# BT5.net
KiCad netlist of a schematic drawn in Altium Designer
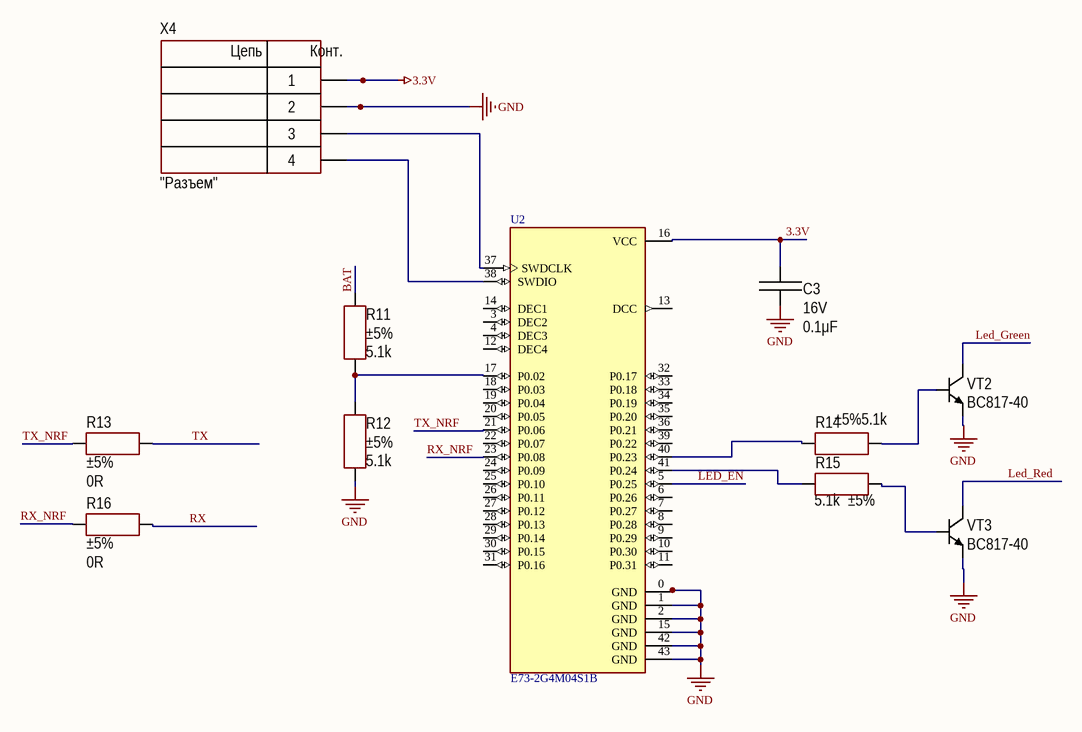
[diagram p0: BT5.SchDoc]

(export (version "E")
  (design (tool "Eeschema 10.0.6"))
  (components
    (comp (ref "C3")
      (value "0.1μF")
      (footprint "standard-case:CAP: 0805")
      (fields
        (field (name "MANUFACTURER") "Yageo")
        (field (name "PARTNUMBER") "CC0805KRX7R7BB104")
        (field (name "VALUEMANUFACTURERPARTNUMBER") "Ceramic capacitor, 0.1μF, X7R, ±10%, 16V, 0805, -55...+125°C")
        (field (name "VOLTAGE") "16V")
      )
      (libsource (lib "capacitor") (part "Ceramic_0805"))
    )
    (comp (ref "R11")
      (value "5.1k")
      (footprint "standard-case:RES: 0805")
      (fields
        (field (name "MANUFACTURER") "Yageo")
        (field (name "PARTNUMBER") "RC0805JR-075K1L")
        (field (name "VALUEMANUFACTURERPARTNUMBER") "Resistor film, 5.1k, ±5%, 0805, 0.125W, -55...+125°C")
        (field (name "TOLERANCE") "±5%")
      )
      (libsource (lib "resistor") (part "Resistor_0805"))
    )
    (comp (ref "R12")
      (value "5.1k")
      (footprint "standard-case:RES: 0805")
      (fields
        (field (name "MANUFACTURER") "Yageo")
        (field (name "PARTNUMBER") "RC0805JR-075K1L")
        (field (name "VALUEMANUFACTURERPARTNUMBER") "Resistor film, 5.1k, ±5%, 0805, 0.125W, -55...+125°C")
        (field (name "TOLERANCE") "±5%")
      )
      (libsource (lib "resistor") (part "Resistor_0805"))
    )
    (comp (ref "R13")
      (value "0R")
      (footprint "standard-case:RES: 0805")
      (fields
        (field (name "MANUFACTURER") "Yageo")
        (field (name "PARTNUMBER") "RC0805JR-070RL")
        (field (name "VALUEMANUFACTURERPARTNUMBER") "Resistor film, 0R, ±5%, 0805, 0.125W, -55...+125°C")
        (field (name "TOLERANCE") "±5%")
      )
      (libsource (lib "") (part "Resistor_0805_1"))
    )
    (comp (ref "R14")
      (value "5.1k")
      (footprint "standard-case:RES: 0805")
      (fields
        (field (name "MANUFACTURER") "Yageo")
        (field (name "PARTNUMBER") "RC0805JR-075K1L")
        (field (name "VALUEMANUFACTURERPARTNUMBER") "Resistor film, 5.1k, ±5%, 0805, 0.125W, -55...+125°C")
        (field (name "TOLERANCE") "±5%")
      )
      (libsource (lib "") (part "Resistor_0805_1"))
    )
    (comp (ref "R15")
      (value "5.1k")
      (footprint "standard-case:RES: 0805")
      (fields
        (field (name "MANUFACTURER") "Yageo")
        (field (name "PARTNUMBER") "RC0805JR-075K1L")
        (field (name "VALUEMANUFACTURERPARTNUMBER") "Resistor film, 5.1k, ±5%, 0805, 0.125W, -55...+125°C")
        (field (name "TOLERANCE") "±5%")
      )
      (libsource (lib "") (part "Resistor_0805_1"))
    )
    (comp (ref "R16")
      (value "0R")
      (footprint "standard-case:RES: 0805")
      (fields
        (field (name "MANUFACTURER") "Yageo")
        (field (name "PARTNUMBER") "RC0805JR-070RL")
        (field (name "VALUEMANUFACTURERPARTNUMBER") "Resistor film, 0R, ±5%, 0805, 0.125W, -55...+125°C")
        (field (name "TOLERANCE") "±5%")
      )
      (libsource (lib "") (part "Resistor_0805_1"))
    )
    (comp (ref "U2")
      (value "E73-2G4M04S1B")
      (footprint "XCVR_E73-2G4M04S1B:XCVR_E73-2G4M04S1B")
      (description "nRF52832 BLE 4.2/5.0 SMD Wireless Module")
      (fields
        (field (name "MF") "EBYTE")
        (field (name "BUYPART") "https://www.snapeda.com/parts/E73-2G4M04S1B/EBYTE/view-part/4219264/?ref=eda")
      )
      (libsource (lib "E73-2G4M04S1B") (part "E73-2G4M04S1B"))
    )
    (comp (ref "VT2")
      (value "~")
      (footprint "standard-case:SOT23")
      (fields
        (field (name "MANUFACTURER") "ON Semiconductor")
        (field (name "VALUEMANUFACTURERPARTNUMBER") "NPN transistor, 45V, 100mA, 100MHz, 250mW, 0.6V, 420, SOT-23, -55...+125°C")
        (field (name "PARTNUMBER") "ВС817-40")
      )
      (libsource (lib "transistor") (part "BJT_NPN_132"))
    )
    (comp (ref "VT3")
      (value "~")
      (footprint "standard-case:SOT23")
      (fields
        (field (name "MANUFACTURER") "ON Semiconductor")
        (field (name "VALUEMANUFACTURERPARTNUMBER") "NPN transistor, 45V, 100mA, 100MHz, 250mW, 0.6V, 420, SOT-23, -55...+125°C")
        (field (name "PARTNUMBER") "ВС817-40")
      )
      (libsource (lib "transistor") (part "BJT_NPN_132"))
    )
    (comp (ref "X4")
      (value "~")
      (footprint "custom-case:CON: PLS-4")
      (fields
        (field (name "MANUFACTURER") "Connfly")
        (field (name "VALUEMANUFACTURERPARTNUMBER") "Connector, 4pin, 2.54mm, 500VAC, 3A")
        (field (name "PARTNUMBER") "PLS-4")
        (field (name "COMMENTTEXT") "\"Разъем\"")
      )
      (libsource (lib "connector") (part "PLS-4"))
    )
  )
  (nets
    (net (code "1") (name "/BAT") (class "Default")
      (node (ref "R11") (pin "1") (pinfunction "1_1") (pintype "passive"))
    )
    (net (code "2") (name "/LED_EN") (class "Default")
      (node (ref "U2") (pin "5") (pinfunction "P0.25_5") (pintype "bidirectional"))
    )
    (net (code "3") (name "/Led_Green") (class "Default")
      (node (ref "VT2") (pin "3") (pinfunction "C_3") (pintype "passive"))
    )
    (net (code "4") (name "/Led_Red") (class "Default")
      (node (ref "VT3") (pin "3") (pinfunction "C_3") (pintype "passive"))
    )
    (net (code "5") (name "/RX") (class "Default")
      (node (ref "R16") (pin "2") (pinfunction "2_2") (pintype "passive"))
    )
    (net (code "6") (name "/RX_NRF") (class "Default")
      (node (ref "R16") (pin "1") (pinfunction "1_1") (pintype "passive"))
      (node (ref "U2") (pin "23") (pinfunction "P0.08_23") (pintype "bidirectional"))
    )
    (net (code "7") (name "/TX") (class "Default")
      (node (ref "R13") (pin "2") (pinfunction "2_2") (pintype "passive"))
    )
    (net (code "8") (name "/TX_NRF") (class "Default")
      (node (ref "R13") (pin "1") (pinfunction "1_1") (pintype "passive"))
      (node (ref "U2") (pin "21") (pinfunction "P0.06_21") (pintype "bidirectional"))
    )
    (net (code "9") (name "3.3V") (class "Default")
      (node (ref "C3") (pin "2") (pinfunction "2_2") (pintype "passive"))
      (node (ref "U2") (pin "16") (pinfunction "VCC_16") (pintype "power_in"))
      (node (ref "X4") (pin "1") (pinfunction "1_1") (pintype "passive"))
    )
    (net (code "10") (name "GND") (class "Default")
      (node (ref "C3") (pin "1") (pinfunction "1_1") (pintype "passive"))
      (node (ref "R12") (pin "2") (pinfunction "2_2") (pintype "passive"))
      (node (ref "U2") (pin "0") (pinfunction "GND_0") (pintype "power_in"))
      (node (ref "U2") (pin "1") (pinfunction "GND_1") (pintype "power_in"))
      (node (ref "U2") (pin "15") (pinfunction "GND_15") (pintype "power_in"))
      (node (ref "U2") (pin "2") (pinfunction "GND_2") (pintype "power_in"))
      (node (ref "U2") (pin "42") (pinfunction "GND_42") (pintype "power_in"))
      (node (ref "U2") (pin "43") (pinfunction "GND_43") (pintype "power_in"))
      (node (ref "VT2") (pin "2") (pinfunction "E_2") (pintype "passive"))
      (node (ref "VT3") (pin "2") (pinfunction "E_2") (pintype "passive"))
      (node (ref "X4") (pin "2") (pinfunction "2_2") (pintype "passive"))
    )
    (net (code "11") (name "Net-(U2-P0.02)") (class "Default")
      (node (ref "R11") (pin "2") (pinfunction "2_2") (pintype "passive"))
      (node (ref "R12") (pin "1") (pinfunction "1_1") (pintype "passive"))
      (node (ref "U2") (pin "17") (pinfunction "P0.02_17") (pintype "bidirectional"))
    )
    (net (code "12") (name "Net-(U2-P0.23)") (class "Default")
      (node (ref "R14") (pin "1") (pinfunction "1_1") (pintype "passive"))
      (node (ref "U2") (pin "40") (pinfunction "P0.23_40") (pintype "bidirectional"))
    )
    (net (code "13") (name "Net-(U2-P0.24)") (class "Default")
      (node (ref "R15") (pin "1") (pinfunction "1_1") (pintype "passive"))
      (node (ref "U2") (pin "41") (pinfunction "P0.24_41") (pintype "bidirectional"))
    )
    (net (code "14") (name "Net-(U2-SWDCLK)") (class "Default")
      (node (ref "U2") (pin "37") (pinfunction "SWDCLK_37") (pintype "input"))
      (node (ref "X4") (pin "3") (pinfunction "3_3") (pintype "power_in"))
    )
    (net (code "15") (name "Net-(U2-SWDIO)") (class "Default")
      (node (ref "U2") (pin "38") (pinfunction "SWDIO_38") (pintype "bidirectional"))
      (node (ref "X4") (pin "4") (pinfunction "4_4") (pintype "power_in"))
    )
    (net (code "16") (name "Net-(VT2-B)") (class "Default")
      (node (ref "R14") (pin "2") (pinfunction "2_2") (pintype "passive"))
      (node (ref "VT2") (pin "1") (pinfunction "B_1") (pintype "passive"))
    )
    (net (code "17") (name "Net-(VT3-B)") (class "Default")
      (node (ref "R15") (pin "2") (pinfunction "2_2") (pintype "passive"))
      (node (ref "VT3") (pin "1") (pinfunction "B_1") (pintype "passive"))
    )
    (net (code "18") (name "unconnected-(U2-DCC-Pad13)") (class "Default")
      (node (ref "U2") (pin "13") (pinfunction "DCC_13") (pintype "output"))
    )
    (net (code "19") (name "unconnected-(U2-DEC1-Pad14)") (class "Default")
      (node (ref "U2") (pin "14") (pinfunction "DEC1_14") (pintype "bidirectional"))
    )
    (net (code "20") (name "unconnected-(U2-DEC2-Pad3)") (class "Default")
      (node (ref "U2") (pin "3") (pinfunction "DEC2_3") (pintype "bidirectional"))
    )
    (net (code "21") (name "unconnected-(U2-DEC3-Pad4)") (class "Default")
      (node (ref "U2") (pin "4") (pinfunction "DEC3_4") (pintype "bidirectional"))
    )
    (net (code "22") (name "unconnected-(U2-DEC4-Pad12)") (class "Default")
      (node (ref "U2") (pin "12") (pinfunction "DEC4_12") (pintype "bidirectional"))
    )
    (net (code "23") (name "unconnected-(U2-P0.03-Pad18)") (class "Default")
      (node (ref "U2") (pin "18") (pinfunction "P0.03_18") (pintype "bidirectional"))
    )
    (net (code "24") (name "unconnected-(U2-P0.04-Pad19)") (class "Default")
      (node (ref "U2") (pin "19") (pinfunction "P0.04_19") (pintype "bidirectional"))
    )
    (net (code "25") (name "unconnected-(U2-P0.05-Pad20)") (class "Default")
      (node (ref "U2") (pin "20") (pinfunction "P0.05_20") (pintype "bidirectional"))
    )
    (net (code "26") (name "unconnected-(U2-P0.07-Pad22)") (class "Default")
      (node (ref "U2") (pin "22") (pinfunction "P0.07_22") (pintype "bidirectional"))
    )
    (net (code "27") (name "unconnected-(U2-P0.09-Pad24)") (class "Default")
      (node (ref "U2") (pin "24") (pinfunction "P0.09_24") (pintype "bidirectional"))
    )
    (net (code "28") (name "unconnected-(U2-P0.10-Pad25)") (class "Default")
      (node (ref "U2") (pin "25") (pinfunction "P0.10_25") (pintype "bidirectional"))
    )
    (net (code "29") (name "unconnected-(U2-P0.11-Pad26)") (class "Default")
      (node (ref "U2") (pin "26") (pinfunction "P0.11_26") (pintype "bidirectional"))
    )
    (net (code "30") (name "unconnected-(U2-P0.12-Pad27)") (class "Default")
      (node (ref "U2") (pin "27") (pinfunction "P0.12_27") (pintype "bidirectional"))
    )
    (net (code "31") (name "unconnected-(U2-P0.13-Pad28)") (class "Default")
      (node (ref "U2") (pin "28") (pinfunction "P0.13_28") (pintype "bidirectional"))
    )
    (net (code "32") (name "unconnected-(U2-P0.14-Pad29)") (class "Default")
      (node (ref "U2") (pin "29") (pinfunction "P0.14_29") (pintype "bidirectional"))
    )
    (net (code "33") (name "unconnected-(U2-P0.15-Pad30)") (class "Default")
      (node (ref "U2") (pin "30") (pinfunction "P0.15_30") (pintype "bidirectional"))
    )
    (net (code "34") (name "unconnected-(U2-P0.16-Pad31)") (class "Default")
      (node (ref "U2") (pin "31") (pinfunction "P0.16_31") (pintype "bidirectional"))
    )
    (net (code "35") (name "unconnected-(U2-P0.17-Pad32)") (class "Default")
      (node (ref "U2") (pin "32") (pinfunction "P0.17_32") (pintype "bidirectional"))
    )
    (net (code "36") (name "unconnected-(U2-P0.18-Pad33)") (class "Default")
      (node (ref "U2") (pin "33") (pinfunction "P0.18_33") (pintype "bidirectional"))
    )
    (net (code "37") (name "unconnected-(U2-P0.19-Pad34)") (class "Default")
      (node (ref "U2") (pin "34") (pinfunction "P0.19_34") (pintype "bidirectional"))
    )
    (net (code "38") (name "unconnected-(U2-P0.20-Pad35)") (class "Default")
      (node (ref "U2") (pin "35") (pinfunction "P0.20_35") (pintype "bidirectional"))
    )
    (net (code "39") (name "unconnected-(U2-P0.21-Pad36)") (class "Default")
      (node (ref "U2") (pin "36") (pinfunction "P0.21_36") (pintype "bidirectional"))
    )
    (net (code "40") (name "unconnected-(U2-P0.22-Pad39)") (class "Default")
      (node (ref "U2") (pin "39") (pinfunction "P0.22_39") (pintype "bidirectional"))
    )
    (net (code "41") (name "unconnected-(U2-P0.26-Pad6)") (class "Default")
      (node (ref "U2") (pin "6") (pinfunction "P0.26_6") (pintype "bidirectional"))
    )
    (net (code "42") (name "unconnected-(U2-P0.27-Pad7)") (class "Default")
      (node (ref "U2") (pin "7") (pinfunction "P0.27_7") (pintype "bidirectional"))
    )
    (net (code "43") (name "unconnected-(U2-P0.28-Pad8)") (class "Default")
      (node (ref "U2") (pin "8") (pinfunction "P0.28_8") (pintype "bidirectional"))
    )
    (net (code "44") (name "unconnected-(U2-P0.29-Pad9)") (class "Default")
      (node (ref "U2") (pin "9") (pinfunction "P0.29_9") (pintype "bidirectional"))
    )
    (net (code "45") (name "unconnected-(U2-P0.30-Pad10)") (class "Default")
      (node (ref "U2") (pin "10") (pinfunction "P0.30_10") (pintype "bidirectional"))
    )
    (net (code "46") (name "unconnected-(U2-P0.31-Pad11)") (class "Default")
      (node (ref "U2") (pin "11") (pinfunction "P0.31_11") (pintype "bidirectional"))
    )
  )
)
